# StemsField_V1_0.net
KiCad netlist of a schematic drawn in EAGLE
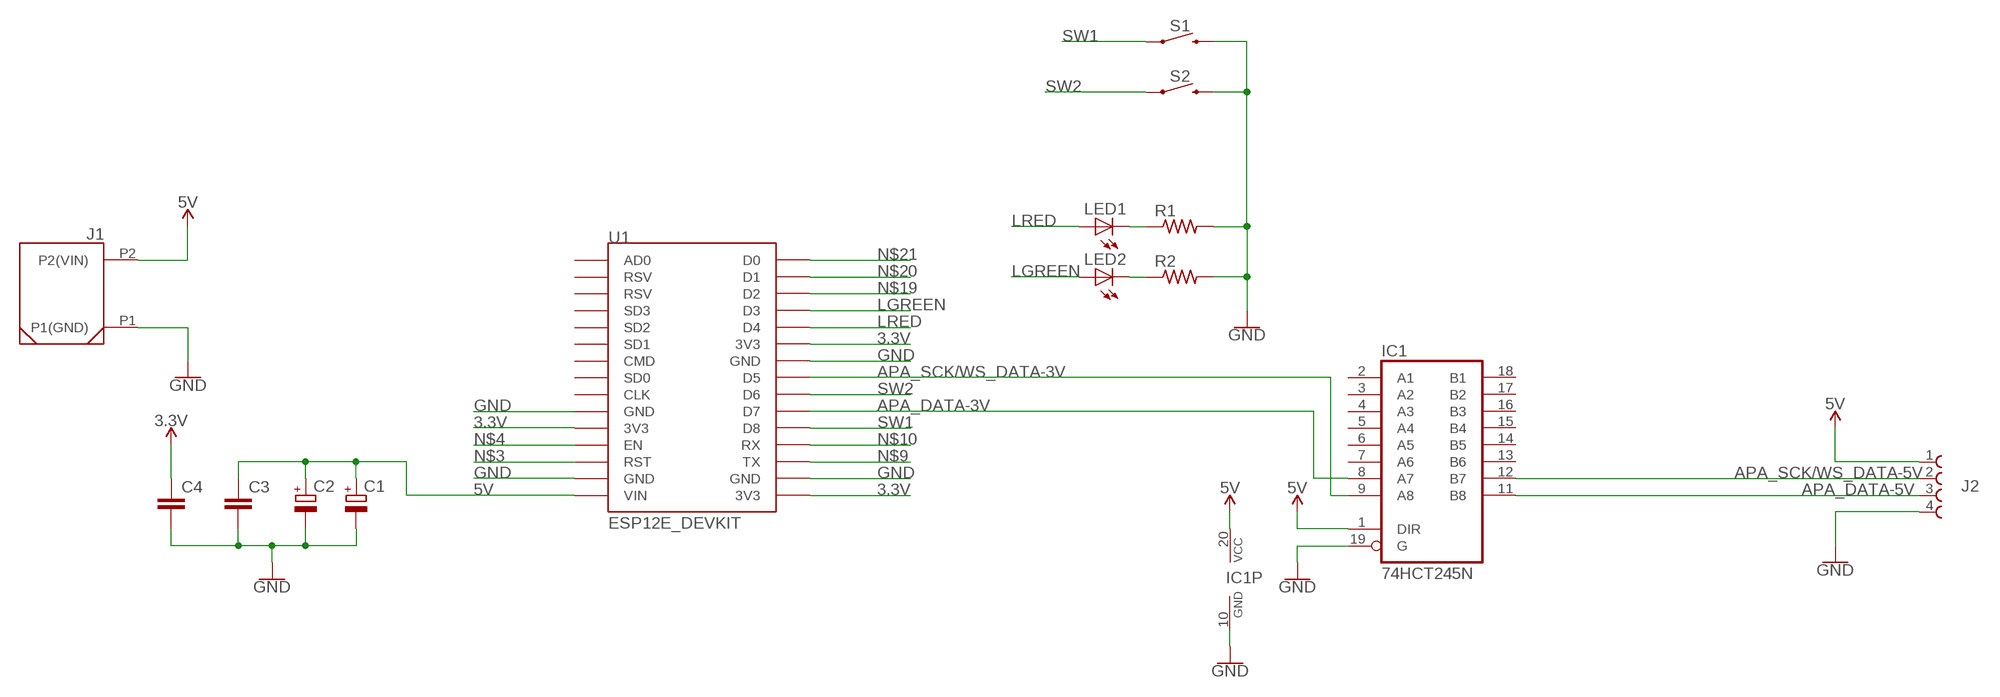
[diagram p0: schematic, sheet 1]

(export (version "E")
  (design (tool "Eeschema 10.0.6"))
  (components
    (comp (ref "C1")
      (value "CPOL-EUE3.5-8")
      (footprint "eagle-import:E3,5-8")
      (libsource (lib "eagle-import") (part "CPOL-EUE3.5-8"))
    )
    (comp (ref "C2")
      (value "CPOL-EUE3.5-8")
      (footprint "eagle-import:E3,5-8")
      (libsource (lib "eagle-import") (part "CPOL-EUE3.5-8"))
    )
    (comp (ref "C3")
      (value "C-EU025-024X044")
      (footprint "eagle-import:C025-024X044")
      (libsource (lib "eagle-import") (part "C-EU025-024X044"))
    )
    (comp (ref "C4")
      (value "C-EU025-024X044")
      (footprint "eagle-import:C025-024X044")
      (libsource (lib "eagle-import") (part "C-EU025-024X044"))
    )
    (comp (ref "IC1")
      (value "74HCT245N")
      (footprint "eagle-import:DIL20")
      (fields (field (name "SPICEPREFIX") "X"))
      (libsource (lib "eagle-import") (part "74245NHCT"))
    )
    (comp (ref "J1")
      (value "XT30PWM")
      (footprint "eagle-import:XT30PW-M")
      (libsource (lib "eagle-import") (part "XT30PWM"))
    )
    (comp (ref "J2")
      (value "691213500004")
      (footprint "eagle-import:691213500004")
      (libsource (lib "eagle-import") (part "691213500004"))
    )
    (comp (ref "LED1")
      (value "LED3MM")
      (footprint "eagle-import:LED3MM")
      (libsource (lib "eagle-import") (part "LED3MM"))
    )
    (comp (ref "LED2")
      (value "LED3MM")
      (footprint "eagle-import:LED3MM")
      (libsource (lib "eagle-import") (part "LED3MM"))
    )
    (comp (ref "R1")
      (value "R-US_0204/5")
      (footprint "eagle-import:0204_5")
      (libsource (lib "eagle-import") (part "R-US_0204/5"))
    )
    (comp (ref "R2")
      (value "R-US_0204/5")
      (footprint "eagle-import:0204_5")
      (libsource (lib "eagle-import") (part "R-US_0204/5"))
    )
    (comp (ref "S1")
      (value "MOMENTARY-SWITCH-SPST-PTH-6.0MM")
      (footprint "eagle-import:TACTILE_SWITCH_PTH_6.0MM")
      (libsource (lib "eagle-import") (part "MOMENTARY-SWITCH-SPST-PTH-6.0MM"))
    )
    (comp (ref "S2")
      (value "MOMENTARY-SWITCH-SPST-PTH-6.0MM")
      (footprint "eagle-import:TACTILE_SWITCH_PTH_6.0MM")
      (libsource (lib "eagle-import") (part "MOMENTARY-SWITCH-SPST-PTH-6.0MM"))
    )
    (comp (ref "U1")
      (value "ESP12E_DEVKIT")
      (footprint "eagle-import:ESP12E_DEVKIT")
      (libsource (lib "eagle-import") (part "ESP12E_DEVKIT"))
    )
  )
  (nets
    (net (code "1") (name "/APA_DATA-3V") (class "Default")
      (node (ref "IC1") (pin "8") (pinfunction "A7_8") (pintype "bidirectional"))
      (node (ref "U1") (pin "D7") (pinfunction "D7_D7") (pintype "bidirectional"))
    )
    (net (code "2") (name "/APA_DATA-5V") (class "Default")
      (node (ref "IC1") (pin "11") (pinfunction "B8_11") (pintype "bidirectional"))
      (node (ref "J2") (pin "3") (pinfunction "2_3") (pintype "passive"))
    )
    (net (code "3") (name "/APA_SCK{slash}WS_DATA-3V") (class "Default")
      (node (ref "IC1") (pin "9") (pinfunction "A8_9") (pintype "bidirectional"))
      (node (ref "U1") (pin "D5") (pinfunction "D5_D5") (pintype "bidirectional"))
    )
    (net (code "4") (name "/APA_SCK{slash}WS_DATA-5V") (class "Default")
      (node (ref "IC1") (pin "12") (pinfunction "B7_12") (pintype "bidirectional"))
      (node (ref "J2") (pin "2") (pinfunction "3_2") (pintype "passive"))
    )
    (net (code "5") (name "/LGREEN") (class "Default")
      (node (ref "LED2") (pin "A") (pinfunction "A_A") (pintype "passive"))
      (node (ref "U1") (pin "D3") (pinfunction "D3_D3") (pintype "bidirectional"))
    )
    (net (code "6") (name "/LRED") (class "Default")
      (node (ref "LED1") (pin "A") (pinfunction "A_A") (pintype "passive"))
      (node (ref "U1") (pin "D4") (pinfunction "D4_D4") (pintype "bidirectional"))
    )
    (net (code "7") (name "/N$3") (class "Default")
      (node (ref "U1") (pin "RST") (pinfunction "RST_RST") (pintype "bidirectional"))
    )
    (net (code "8") (name "/N$4") (class "Default")
      (node (ref "U1") (pin "EN") (pinfunction "EN_EN") (pintype "bidirectional"))
    )
    (net (code "9") (name "/N$9") (class "Default")
      (node (ref "U1") (pin "TX") (pinfunction "TX_TX") (pintype "bidirectional"))
    )
    (net (code "10") (name "/N$10") (class "Default")
      (node (ref "U1") (pin "RX") (pinfunction "RX_RX") (pintype "bidirectional"))
    )
    (net (code "11") (name "/N$19") (class "Default")
      (node (ref "U1") (pin "D2") (pinfunction "D2_D2") (pintype "bidirectional"))
    )
    (net (code "12") (name "/N$20") (class "Default")
      (node (ref "U1") (pin "D1") (pinfunction "D1_D1") (pintype "bidirectional"))
    )
    (net (code "13") (name "/N$21") (class "Default")
      (node (ref "U1") (pin "D0") (pinfunction "D0_D0") (pintype "bidirectional"))
    )
    (net (code "14") (name "/SW1") (class "Default")
      (node (ref "S1") (pin "1") (pinfunction "1_1") (pintype "passive"))
      (node (ref "U1") (pin "D8") (pinfunction "D8_D8") (pintype "bidirectional"))
    )
    (net (code "15") (name "/SW2") (class "Default")
      (node (ref "S2") (pin "1") (pinfunction "1_1") (pintype "passive"))
      (node (ref "U1") (pin "D6") (pinfunction "D6_D6") (pintype "bidirectional"))
    )
    (net (code "16") (name "3.3V") (class "Default")
      (node (ref "C4") (pin "1") (pinfunction "1_1") (pintype "passive"))
      (node (ref "U1") (pin "3V3@0") (pinfunction "3V3_3V3@0") (pintype "bidirectional"))
      (node (ref "U1") (pin "3V3@1") (pinfunction "3V3_3V3@1") (pintype "bidirectional"))
      (node (ref "U1") (pin "3V3@2") (pinfunction "3V3_3V3@2") (pintype "bidirectional"))
    )
    (net (code "17") (name "5V") (class "Default")
      (node (ref "C1") (pin "+") (pinfunction "+_+") (pintype "passive"))
      (node (ref "C2") (pin "+") (pinfunction "+_+") (pintype "passive"))
      (node (ref "C3") (pin "1") (pinfunction "1_1") (pintype "passive"))
      (node (ref "IC1") (pin "1") (pinfunction "DIR_1") (pintype "input"))
      (node (ref "IC1") (pin "20") (pinfunction "VCC_20") (pintype "power_in"))
      (node (ref "J1") (pin "P2") (pinfunction "P2(VIN)_P2") (pintype "bidirectional"))
      (node (ref "J2") (pin "1") (pinfunction "4_1") (pintype "passive"))
      (node (ref "U1") (pin "VIN") (pinfunction "VIN_VIN") (pintype "bidirectional"))
    )
    (net (code "18") (name "GND") (class "Default")
      (node (ref "C1") (pin "-") (pinfunction "-_-") (pintype "passive"))
      (node (ref "C2") (pin "-") (pinfunction "-_-") (pintype "passive"))
      (node (ref "C3") (pin "2") (pinfunction "2_2") (pintype "passive"))
      (node (ref "C4") (pin "2") (pinfunction "2_2") (pintype "passive"))
      (node (ref "IC1") (pin "10") (pinfunction "GND_10") (pintype "power_in"))
      (node (ref "IC1") (pin "19") (pinfunction "G_19") (pintype "input"))
      (node (ref "J1") (pin "P1") (pinfunction "P1(GND)_P1") (pintype "bidirectional"))
      (node (ref "J2") (pin "4") (pinfunction "1_4") (pintype "passive"))
      (node (ref "R1") (pin "2") (pinfunction "2_2") (pintype "passive"))
      (node (ref "R2") (pin "2") (pinfunction "2_2") (pintype "passive"))
      (node (ref "S1") (pin "3") (pinfunction "2_3") (pintype "passive"))
      (node (ref "S2") (pin "3") (pinfunction "2_3") (pintype "passive"))
      (node (ref "U1") (pin "GND@0") (pinfunction "GND_GND@0") (pintype "bidirectional"))
      (node (ref "U1") (pin "GND@1") (pinfunction "GND_GND@1") (pintype "bidirectional"))
      (node (ref "U1") (pin "GND@2") (pinfunction "GND_GND@2") (pintype "bidirectional"))
      (node (ref "U1") (pin "GND@3") (pinfunction "GND_GND@3") (pintype "bidirectional"))
    )
    (net (code "19") (name "Net-(LED1-C)") (class "Default")
      (node (ref "LED1") (pin "K") (pinfunction "C_K") (pintype "passive"))
      (node (ref "R1") (pin "1") (pinfunction "1_1") (pintype "passive"))
    )
    (net (code "20") (name "Net-(LED2-C)") (class "Default")
      (node (ref "LED2") (pin "K") (pinfunction "C_K") (pintype "passive"))
      (node (ref "R2") (pin "1") (pinfunction "1_1") (pintype "passive"))
    )
    (net (code "21") (name "unconnected-(IC1A-A1-Pad2)") (class "Default")
      (node (ref "IC1") (pin "2") (pinfunction "A1_2") (pintype "bidirectional"))
    )
    (net (code "22") (name "unconnected-(IC1A-A2-Pad3)") (class "Default")
      (node (ref "IC1") (pin "3") (pinfunction "A2_3") (pintype "bidirectional"))
    )
    (net (code "23") (name "unconnected-(IC1A-A3-Pad4)") (class "Default")
      (node (ref "IC1") (pin "4") (pinfunction "A3_4") (pintype "bidirectional"))
    )
    (net (code "24") (name "unconnected-(IC1A-A4-Pad5)") (class "Default")
      (node (ref "IC1") (pin "5") (pinfunction "A4_5") (pintype "bidirectional"))
    )
    (net (code "25") (name "unconnected-(IC1A-A5-Pad6)") (class "Default")
      (node (ref "IC1") (pin "6") (pinfunction "A5_6") (pintype "bidirectional"))
    )
    (net (code "26") (name "unconnected-(IC1A-A6-Pad7)") (class "Default")
      (node (ref "IC1") (pin "7") (pinfunction "A6_7") (pintype "bidirectional"))
    )
    (net (code "27") (name "unconnected-(IC1A-B1-Pad18)") (class "Default")
      (node (ref "IC1") (pin "18") (pinfunction "B1_18") (pintype "bidirectional"))
    )
    (net (code "28") (name "unconnected-(IC1A-B2-Pad17)") (class "Default")
      (node (ref "IC1") (pin "17") (pinfunction "B2_17") (pintype "bidirectional"))
    )
    (net (code "29") (name "unconnected-(IC1A-B3-Pad16)") (class "Default")
      (node (ref "IC1") (pin "16") (pinfunction "B3_16") (pintype "bidirectional"))
    )
    (net (code "30") (name "unconnected-(IC1A-B4-Pad15)") (class "Default")
      (node (ref "IC1") (pin "15") (pinfunction "B4_15") (pintype "bidirectional"))
    )
    (net (code "31") (name "unconnected-(IC1A-B5-Pad14)") (class "Default")
      (node (ref "IC1") (pin "14") (pinfunction "B5_14") (pintype "bidirectional"))
    )
    (net (code "32") (name "unconnected-(IC1A-B6-Pad13)") (class "Default")
      (node (ref "IC1") (pin "13") (pinfunction "B6_13") (pintype "bidirectional"))
    )
    (net (code "33") (name "unconnected-(U1-PadAD0)") (class "Default")
      (node (ref "U1") (pin "AD0") (pinfunction "AD0_AD0") (pintype "bidirectional"))
    )
    (net (code "34") (name "unconnected-(U1-PadCLK)") (class "Default")
      (node (ref "U1") (pin "CLK") (pinfunction "CLK_CLK") (pintype "bidirectional"))
    )
    (net (code "35") (name "unconnected-(U1-PadCMD)") (class "Default")
      (node (ref "U1") (pin "CMD") (pinfunction "CMD_CMD") (pintype "bidirectional"))
    )
    (net (code "36") (name "unconnected-(U1-PadSD0)") (class "Default")
      (node (ref "U1") (pin "SD0") (pinfunction "SD0_SD0") (pintype "bidirectional"))
    )
    (net (code "37") (name "unconnected-(U1-PadSD1)") (class "Default")
      (node (ref "U1") (pin "SD1") (pinfunction "SD1_SD1") (pintype "bidirectional"))
    )
    (net (code "38") (name "unconnected-(U1-PadSD2)") (class "Default")
      (node (ref "U1") (pin "SD2") (pinfunction "SD2_SD2") (pintype "bidirectional"))
    )
    (net (code "39") (name "unconnected-(U1-PadSD3)") (class "Default")
      (node (ref "U1") (pin "SD3") (pinfunction "SD3_SD3") (pintype "bidirectional"))
    )
    (net (code "40") (name "unconnected-(U1-RSV-PadRSV@0)") (class "Default")
      (node (ref "U1") (pin "RSV@0") (pinfunction "RSV_RSV@0") (pintype "bidirectional"))
    )
    (net (code "41") (name "unconnected-(U1-RSV-PadRSV@1)") (class "Default")
      (node (ref "U1") (pin "RSV@1") (pinfunction "RSV_RSV@1") (pintype "bidirectional"))
    )
  )
)
